# Buck_Converter.net
KiCad netlist of a schematic drawn in EAGLE
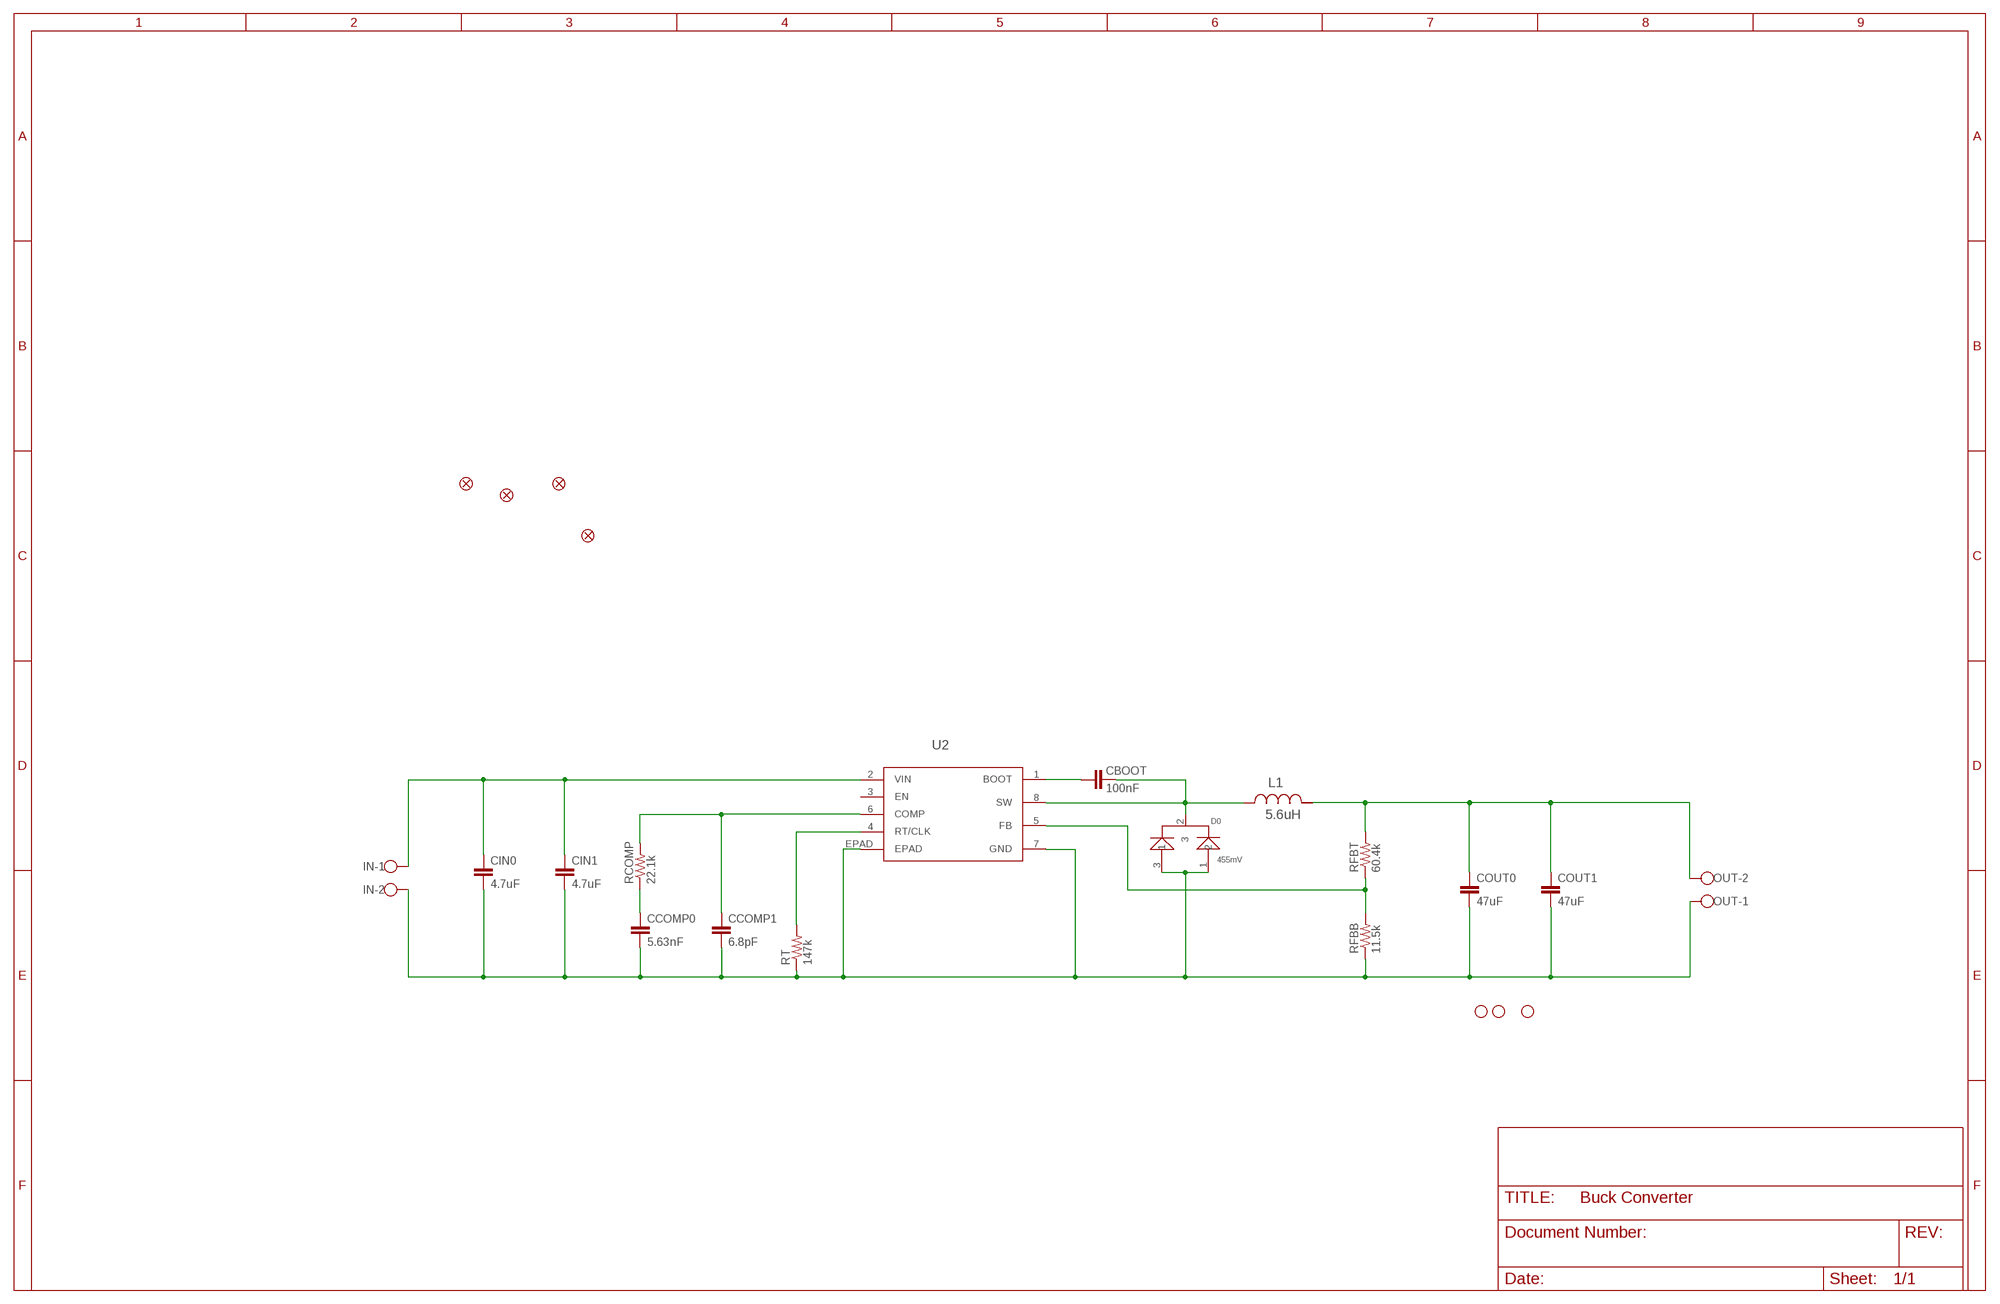
[diagram p0: schematic, sheet 1]

(export (version "E")
  (design (tool "Eeschema 10.0.6"))
  (components
    (comp (ref "CBOOT")
      (value "100nF")
      (footprint "eagle-import:C0805")
      (libsource (lib "eagle-import") (part "resistor_348_C-EUC0805"))
    )
    (comp (ref "CCOMP0")
      (value "5.63nF")
      (footprint "eagle-import:C0805")
      (libsource (lib "eagle-import") (part "resistor_348_C-EUC0805"))
    )
    (comp (ref "CCOMP1")
      (value "6.8pF")
      (footprint "eagle-import:C0805")
      (libsource (lib "eagle-import") (part "resistor_348_C-EUC0805"))
    )
    (comp (ref "CIN0")
      (value "4.7uF")
      (footprint "eagle-import:C0805")
      (libsource (lib "eagle-import") (part "C-EUC0805"))
    )
    (comp (ref "CIN1")
      (value "4.7uF")
      (footprint "eagle-import:C0805")
      (libsource (lib "eagle-import") (part "C-EUC0805"))
    )
    (comp (ref "COUT0")
      (value "47uF")
      (footprint "eagle-import:C1206")
      (libsource (lib "eagle-import") (part "C-EUC1206"))
    )
    (comp (ref "COUT1")
      (value "47uF")
      (footprint "eagle-import:C1206")
      (libsource (lib "eagle-import") (part "C-EUC1206"))
    )
    (comp (ref "D0")
      (value "455mV")
      (footprint "eagle-import:D2PAK-L")
      (fields (field (name "MANUFACTURER_PART_NUMBER") "STPS20M100SGTR"))
      (libsource (lib "eagle-import") (part "STPS20M100SG-TRD2PAK-L"))
    )
    (comp (ref "FD1")
      (value "FIDUCIALUFIDUCIAL")
      (footprint "eagle-import:FIDUCIAL-MICRO")
      (libsource (lib "eagle-import") (part "FIDUCIALUFIDUCIAL"))
    )
    (comp (ref "FD2")
      (value "FIDUCIALUFIDUCIAL")
      (footprint "eagle-import:FIDUCIAL-MICRO")
      (libsource (lib "eagle-import") (part "FIDUCIALUFIDUCIAL"))
    )
    (comp (ref "FD3")
      (value "FIDUCIALUFIDUCIAL")
      (footprint "eagle-import:FIDUCIAL-MICRO")
      (libsource (lib "eagle-import") (part "FIDUCIALUFIDUCIAL"))
    )
    (comp (ref "FD4")
      (value "FIDUCIALUFIDUCIAL")
      (footprint "eagle-import:FIDUCIAL-MICRO")
      (libsource (lib "eagle-import") (part "FIDUCIALUFIDUCIAL"))
    )
    (comp (ref "H1")
      (value "STAND-OFFTIGHT")
      (footprint "eagle-import:STAND-OFF-TIGHT")
      (libsource (lib "eagle-import") (part "STAND-OFFTIGHT"))
    )
    (comp (ref "H2")
      (value "STAND-OFFTIGHT")
      (footprint "eagle-import:STAND-OFF-TIGHT")
      (libsource (lib "eagle-import") (part "STAND-OFFTIGHT"))
    )
    (comp (ref "H3")
      (value "STAND-OFFTIGHT")
      (footprint "eagle-import:STAND-OFF-TIGHT")
      (libsource (lib "eagle-import") (part "STAND-OFFTIGHT"))
    )
    (comp (ref "IN")
      (value "W237-102")
      (footprint "eagle-import:W237-102")
      (fields (field (name "MPN") "237-102"))
      (libsource (lib "eagle-import") (part "W237-102"))
    )
    (comp (ref "L1")
      (value "5.6uH")
      (footprint "eagle-import:SDR1307")
      (fields (field (name "MANUFACTURER_PART_NUMBER") "SDR13075R6ML"))
      (libsource (lib "eagle-import") (part "SDR1307-5R6ML"))
    )
    (comp (ref "OUT")
      (value "W237-102")
      (footprint "eagle-import:W237-102")
      (fields (field (name "MPN") "237-102"))
      (libsource (lib "eagle-import") (part "W237-102"))
    )
    (comp (ref "RCOMP")
      (value "22.1k")
      (footprint "eagle-import:R0603")
      (libsource (lib "eagle-import") (part "R-US_R0603"))
    )
    (comp (ref "RFBB")
      (value "11.5k")
      (footprint "eagle-import:R0603")
      (libsource (lib "eagle-import") (part "R-US_R0603"))
    )
    (comp (ref "RFBT")
      (value "60.4k")
      (footprint "eagle-import:R0603")
      (libsource (lib "eagle-import") (part "R-US_R0603"))
    )
    (comp (ref "RT")
      (value "147k")
      (footprint "eagle-import:R0603")
      (libsource (lib "eagle-import") (part "R-US_R0603"))
    )
    (comp (ref "U2")
      (value "TPS54540DDARDDA8_3P1X2P4-L")
      (footprint "eagle-import:DDA8_3P1X2P4-L")
      (fields (field (name "MANUFACTURER_PART_NUMBER") "TPS54540DDAR"))
      (libsource (lib "eagle-import") (part "TPS54540DDARDDA8_3P1X2P4-L"))
    )
  )
  (nets
    (net (code "1") (name "Net-(CCOMP0-Pad1)") (class "Default")
      (node (ref "CCOMP0") (pin "1") (pinfunction "1_1") (pintype "passive"))
      (node (ref "RCOMP") (pin "1") (pinfunction "1_1") (pintype "passive"))
    )
    (net (code "2") (name "Net-(D0-1)") (class "Default")
      (node (ref "CCOMP0") (pin "2") (pinfunction "2_2") (pintype "passive"))
      (node (ref "CCOMP1") (pin "2") (pinfunction "2_2") (pintype "passive"))
      (node (ref "CIN0") (pin "2") (pinfunction "2_2") (pintype "passive"))
      (node (ref "CIN1") (pin "2") (pinfunction "2_2") (pintype "passive"))
      (node (ref "COUT0") (pin "2") (pinfunction "2_2") (pintype "passive"))
      (node (ref "COUT1") (pin "2") (pinfunction "2_2") (pintype "passive"))
      (node (ref "D0") (pin "1") (pinfunction "2_1") (pintype "passive"))
      (node (ref "D0") (pin "3") (pinfunction "1_3") (pintype "passive"))
      (node (ref "IN") (pin "2") (pinfunction "KL_2") (pintype "passive"))
      (node (ref "OUT") (pin "1") (pinfunction "KL_1") (pintype "passive"))
      (node (ref "RFBB") (pin "1") (pinfunction "1_1") (pintype "passive"))
      (node (ref "RT") (pin "1") (pinfunction "1_1") (pintype "passive"))
      (node (ref "U2") (pin "7") (pinfunction "GND_7") (pintype "power_in"))
      (node (ref "U2") (pin "EPAD") (pinfunction "EPAD_EPAD") (pintype "passive"))
    )
    (net (code "3") (name "Net-(D0-3)") (class "Default")
      (node (ref "CBOOT") (pin "1") (pinfunction "1_1") (pintype "passive"))
      (node (ref "D0") (pin "2") (pinfunction "3_2") (pintype "passive"))
      (node (ref "L1") (pin "1") (pinfunction "1_1") (pintype "passive"))
      (node (ref "U2") (pin "8") (pinfunction "SW_8") (pintype "input"))
    )
    (net (code "4") (name "Net-(INA-KL)") (class "Default")
      (node (ref "CIN0") (pin "1") (pinfunction "1_1") (pintype "passive"))
      (node (ref "CIN1") (pin "1") (pinfunction "1_1") (pintype "passive"))
      (node (ref "IN") (pin "1") (pinfunction "KL_1") (pintype "passive"))
      (node (ref "U2") (pin "2") (pinfunction "VIN_2") (pintype "input"))
    )
    (net (code "5") (name "Net-(OUTB-KL)") (class "Default")
      (node (ref "COUT0") (pin "1") (pinfunction "1_1") (pintype "passive"))
      (node (ref "COUT1") (pin "1") (pinfunction "1_1") (pintype "passive"))
      (node (ref "L1") (pin "2") (pinfunction "2_2") (pintype "passive"))
      (node (ref "OUT") (pin "2") (pinfunction "KL_2") (pintype "passive"))
      (node (ref "RFBT") (pin "2") (pinfunction "2_2") (pintype "passive"))
    )
    (net (code "6") (name "Net-(U2-BOOT)") (class "Default")
      (node (ref "CBOOT") (pin "2") (pinfunction "2_2") (pintype "passive"))
      (node (ref "U2") (pin "1") (pinfunction "BOOT_1") (pintype "output"))
    )
    (net (code "7") (name "Net-(U2-COMP)") (class "Default")
      (node (ref "CCOMP1") (pin "1") (pinfunction "1_1") (pintype "passive"))
      (node (ref "RCOMP") (pin "2") (pinfunction "2_2") (pintype "passive"))
      (node (ref "U2") (pin "6") (pinfunction "COMP_6") (pintype "output"))
    )
    (net (code "8") (name "Net-(U2-FB)") (class "Default")
      (node (ref "RFBB") (pin "2") (pinfunction "2_2") (pintype "passive"))
      (node (ref "RFBT") (pin "1") (pinfunction "1_1") (pintype "passive"))
      (node (ref "U2") (pin "5") (pinfunction "FB_5") (pintype "input"))
    )
    (net (code "9") (name "Net-(U2-RT{slash}CLK)") (class "Default")
      (node (ref "RT") (pin "2") (pinfunction "2_2") (pintype "passive"))
      (node (ref "U2") (pin "4") (pinfunction "RT/CLK_4") (pintype "input"))
    )
    (net (code "10") (name "unconnected-(U2-EN-Pad3)") (class "Default")
      (node (ref "U2") (pin "3") (pinfunction "EN_3") (pintype "input"))
    )
  )
)
